# Relay.net
KiCad netlist of a schematic drawn in Altium Designer
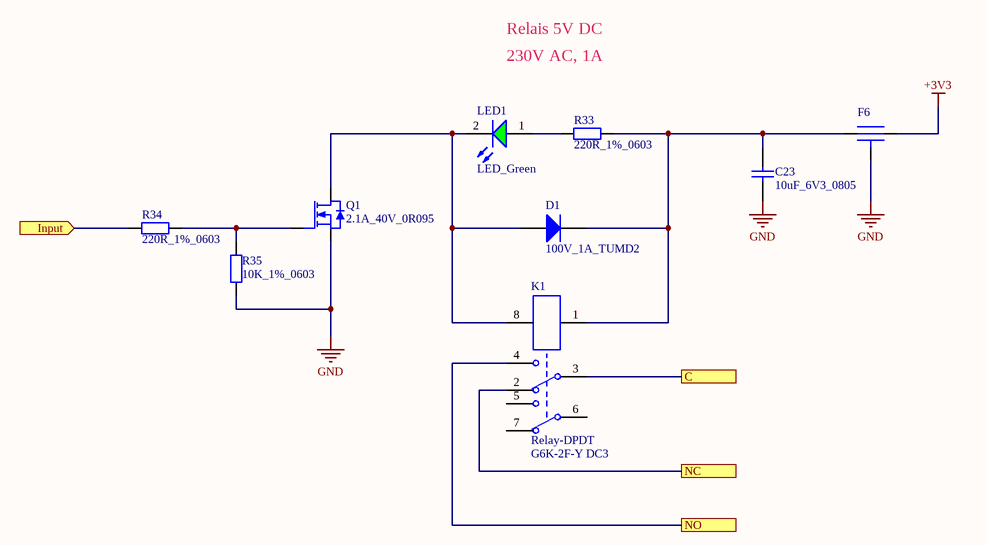
[diagram p0: Relay.SchDoc]

(export (version "E")
  (design (tool "Eeschema 10.0.6"))
  (components
    (comp (ref "C23")
      (value "10uF_6V3_0805")
      (footprint "Common:C0805")
      (description "Capacitor")
      (fields (field (name "MF") " MULTICOMP") (field (name "MPN") "MCTT21X106M6R3CT"))
      (libsource (lib "Common") (part "Cap"))
    )
    (comp (ref "D1")
      (value "100V_1A_TUMD2")
      (footprint "TUMD2")
      (description "Default Diode")
      (fields (field (name "MF") "VISHAY") (field (name "MPN") "MSE1PB-M3/89A"))
      (libsource (lib "Miscellaneous Devices") (part "Diode"))
    )
    (comp (ref "F6")
      (value "EMI")
      (footprint "EMIFIL_0603")
      (description "FILTER CAP 0.1UF 2A 16V 0603")
      (fields (field (name "MF") "MURATA") (field (name "MPN") "NFM18PC104R1C3D"))
      (libsource (lib "Common") (part "EMIFIL_0603"))
    )
    (comp (ref "K1")
      (value "Relay-DPDT")
      (footprint "RELAY_G6K_2F_Y")
      (description "Dual-Pole Dual-Throw Relay")
      (fields (field (name "MF") "Omron Electronics") (field (name "MPN") "G6K-2F-Y DC3"))
      (libsource (lib "Miscellaneous Devices") (part "Relay-DPDT"))
    )
    (comp (ref "LED1")
      (value "LED_Green")
      (footprint "LED_0603_Bright Green")
      (description "SMD mono-color Chip LED, WL-SMCW, Bright Green")
      (fields (field (name "MPN") "150060VS75000") (field (name "MF") "Wurth Elektronik"))
      (libsource (lib "WL-SMCW_rev15b") (part "WL-SMCW 0603  150060VS75000"))
    )
    (comp (ref "Q1")
      (value "2.1A_40V_0R095")
      (footprint "Common:SOT23_N")
      (description "N-Channel MOSFET")
      (fields (field (name "MF") "NEXPERIA") (field (name "MPN") "PMV130ENEA"))
      (libsource (lib "Common") (part "MOSFET-N"))
    )
    (comp (ref "R33")
      (value "220R_1%_0603")
      (footprint "R0603")
      (description "Resistor")
      (fields (field (name "MF") "MULTICOMP") (field (name "MPN") "MCWR06X2200FTL"))
      (libsource (lib "Miscellaneous Devices") (part "Res2"))
    )
    (comp (ref "R34")
      (value "220R_1%_0603")
      (footprint "R0603")
      (description "Resistor")
      (fields (field (name "MF") "MULTICOMP") (field (name "MPN") "MCWR06X2200FTL"))
      (libsource (lib "Miscellaneous Devices") (part "Res2"))
    )
    (comp (ref "R35")
      (value "10K_1%_0603")
      (footprint "R0603")
      (description "Resistor")
      (fields (field (name "MPN") "MCWR06X1002FTL") (field (name "MF") "MULTICOMP"))
      (libsource (lib "Common") (part "RES"))
    )
  )
  (nets
    (net (code "1") (name "+3V3") (class "Default")
      (node (ref "F6") (pin "1") (pinfunction "1_1") (pintype "passive"))
    )
    (net (code "2") (name "/C") (class "Default")
      (node (ref "K1") (pin "3") (pinfunction "4_3") (pintype "passive"))
    )
    (net (code "3") (name "/Input") (class "Default")
      (node (ref "R34") (pin "2") (pinfunction "2_2") (pintype "passive"))
    )
    (net (code "4") (name "/NC") (class "Default")
      (node (ref "K1") (pin "2") (pinfunction "5_2") (pintype "passive"))
    )
    (net (code "5") (name "/NO") (class "Default")
      (node (ref "K1") (pin "4") (pinfunction "6_4") (pintype "passive"))
    )
    (net (code "6") (name "GND") (class "Default")
      (node (ref "C23") (pin "1") (pinfunction "1_1") (pintype "passive"))
      (node (ref "F6") (pin "GND") (pinfunction "GND_GND") (pintype "passive"))
      (node (ref "Q1") (pin "2") (pinfunction "S_2") (pintype "passive"))
      (node (ref "R35") (pin "1") (pinfunction "1_1") (pintype "passive"))
    )
    (net (code "7") (name "Net-(D1-A)") (class "Default")
      (node (ref "D1") (pin "1") (pinfunction "A_1") (pintype "passive"))
      (node (ref "K1") (pin "8") (pinfunction "8_8") (pintype "passive"))
      (node (ref "LED1") (pin "2") (pinfunction "C_2") (pintype "passive"))
      (node (ref "Q1") (pin "3") (pinfunction "D_3") (pintype "passive"))
    )
    (net (code "8") (name "Net-(D1-K)") (class "Default")
      (node (ref "C23") (pin "2") (pinfunction "2_2") (pintype "passive"))
      (node (ref "D1") (pin "2") (pinfunction "K_2") (pintype "passive"))
      (node (ref "F6") (pin "2") (pinfunction "2_2") (pintype "passive"))
      (node (ref "K1") (pin "1") (pinfunction "7_1") (pintype "passive"))
      (node (ref "R33") (pin "1") (pinfunction "1_1") (pintype "passive"))
    )
    (net (code "9") (name "Net-(LED1-A)") (class "Default")
      (node (ref "LED1") (pin "1") (pinfunction "A_1") (pintype "passive"))
      (node (ref "R33") (pin "2") (pinfunction "2_2") (pintype "passive"))
    )
    (net (code "10") (name "Net-(Q1-G)") (class "Default")
      (node (ref "Q1") (pin "1") (pinfunction "G_1") (pintype "passive"))
      (node (ref "R34") (pin "1") (pinfunction "1_1") (pintype "passive"))
      (node (ref "R35") (pin "2") (pinfunction "2_2") (pintype "passive"))
    )
    (net (code "11") (name "unconnected-(K1-1-Pad6)") (class "Default")
      (node (ref "K1") (pin "6") (pinfunction "1_6") (pintype "passive"))
    )
    (net (code "12") (name "unconnected-(K1-2-Pad7)") (class "Default")
      (node (ref "K1") (pin "7") (pinfunction "2_7") (pintype "passive"))
    )
    (net (code "13") (name "unconnected-(K1-3-Pad5)") (class "Default")
      (node (ref "K1") (pin "5") (pinfunction "3_5") (pintype "passive"))
    )
  )
)
